# 05_can_spi.net
KiCad netlist of a schematic drawn in Altium Designer
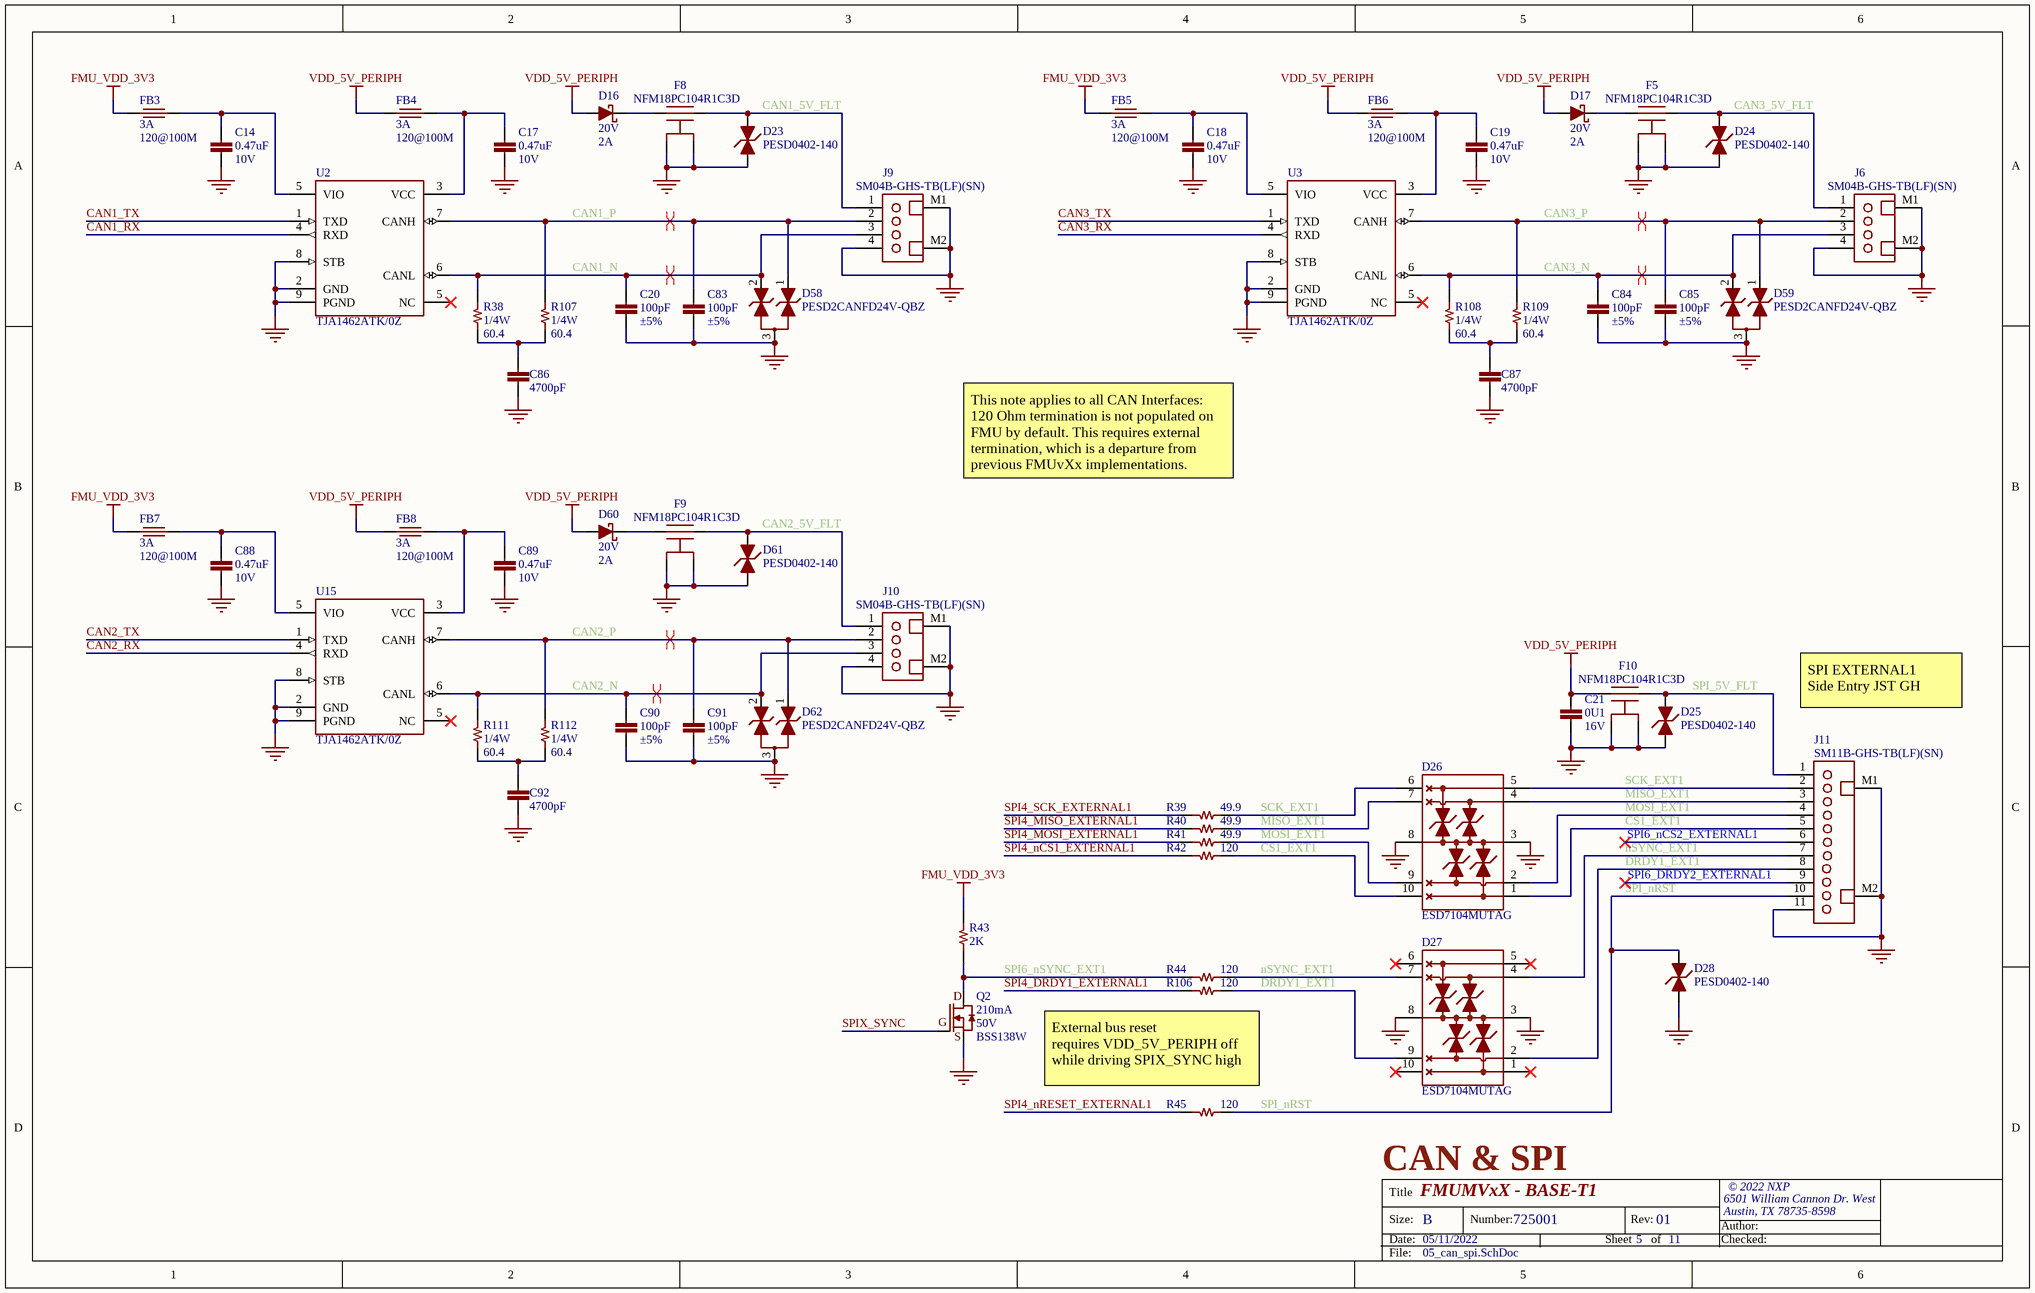
[diagram p0: 05_can_spi.SchDoc]

(export (version "E")
  (design (tool "Eeschema 10.0.6"))
  (components
    (comp (ref "C14")
      (value "0.47uF")
      (footprint "CAPC1608X90L30N")
      (description "CAP CER 0.47UF 10% 10V X7R 0603")
      (fields
        (field (name "TOLERANCE") "±10%")
        (field (name "MANUFACTURER") "Samsung Electro-Mechanics")
        (field (name "VOLTAGE - RATED") "10V")
      )
      (libsource (lib "NscDG_Integrated_Library") (part "CAP_0U47_10V_X7R_0603"))
    )
    (comp (ref "C17")
      (value "0.47uF")
      (footprint "CAPC1608X90L30N")
      (description "CAP CER 0.47UF 10% 10V X7R 0603")
      (fields
        (field (name "TOLERANCE") "±10%")
        (field (name "MANUFACTURER") "Samsung Electro-Mechanics")
        (field (name "VOLTAGE - RATED") "10V")
      )
      (libsource (lib "NscDG_Integrated_Library") (part "CAP_0U47_10V_X7R_0603"))
    )
    (comp (ref "C18")
      (value "0.47uF")
      (footprint "CAPC1608X90L30N")
      (description "CAP CER 0.47UF 10% 10V X7R 0603")
      (fields
        (field (name "TOLERANCE") "±10%")
        (field (name "MANUFACTURER") "Samsung Electro-Mechanics")
        (field (name "VOLTAGE - RATED") "10V")
      )
      (libsource (lib "NscDG_Integrated_Library") (part "CAP_0U47_10V_X7R_0603"))
    )
    (comp (ref "C19")
      (value "0.47uF")
      (footprint "CAPC1608X90L30N")
      (description "CAP CER 0.47UF 10% 10V X7R 0603")
      (fields
        (field (name "TOLERANCE") "±10%")
        (field (name "MANUFACTURER") "Samsung Electro-Mechanics")
        (field (name "VOLTAGE - RATED") "10V")
      )
      (libsource (lib "NscDG_Integrated_Library") (part "CAP_0U47_10V_X7R_0603"))
    )
    (comp (ref "C20")
      (value "100pF")
      (footprint "CAPC100X50X56L25N")
      (description "CAP CER 100PF +/-5% 50V COG/NPO 0402")
      (fields
        (field (name "MANUFACTURER") "Murata Electronics")
        (field (name "MANUFACTURER PART NUMBER") "GRM1555C1H101JA01D")
        (field (name "TOLERANCE") "±5%")
      )
      (libsource (lib "NscDG_Integrated_Library") (part "CAP_100PF_50V_COG/NPO_0402"))
    )
    (comp (ref "C21")
      (value "0U1")
      (footprint "CAPC100X50X56L25N")
      (description "CAP CER 0.1UF 10% 16V X7R 0402")
      (fields
        (field (name "TOLERANCE") "±10%")
        (field (name "MANUFACTURER") "Murata Electronics")
        (field (name "VOLTAGE - RATED") "16V")
      )
      (libsource (lib "NscDG_Integrated_Library") (part "CAP_0U1_16V_X7R_0402"))
    )
    (comp (ref "C83")
      (value "100pF")
      (footprint "CAPC100X50X56L25N")
      (description "CAP CER 100PF +/-5% 50V COG/NPO 0402")
      (fields
        (field (name "MANUFACTURER") "Murata Electronics")
        (field (name "MANUFACTURER PART NUMBER") "GRM1555C1H101JA01D")
        (field (name "TOLERANCE") "±5%")
      )
      (libsource (lib "NscDG_Integrated_Library") (part "CAP_100PF_50V_COG/NPO_0402"))
    )
    (comp (ref "C84")
      (value "100pF")
      (footprint "CAPC100X50X56L25N")
      (description "CAP CER 100PF +/-5% 50V COG/NPO 0402")
      (fields
        (field (name "MANUFACTURER") "Murata Electronics")
        (field (name "MANUFACTURER PART NUMBER") "GRM1555C1H101JA01D")
        (field (name "TOLERANCE") "±5%")
      )
      (libsource (lib "NscDG_Integrated_Library") (part "CAP_100PF_50V_COG/NPO_0402"))
    )
    (comp (ref "C85")
      (value "100pF")
      (footprint "CAPC100X50X56L25N")
      (description "CAP CER 100PF +/-5% 50V COG/NPO 0402")
      (fields
        (field (name "MANUFACTURER") "Murata Electronics")
        (field (name "MANUFACTURER PART NUMBER") "GRM1555C1H101JA01D")
        (field (name "TOLERANCE") "±5%")
      )
      (libsource (lib "NscDG_Integrated_Library") (part "CAP_100PF_50V_COG/NPO_0402"))
    )
    (comp (ref "C86")
      (value "4700pF")
      (footprint "CAPC100X50X56L25N")
      (description "CAP CER 4700PF 10% 50V X7R 0402")
      (fields
        (field (name "MANUFACTURER") "Murata Electronics")
        (field (name "MANUFACTURER PART NUMBER") "GRM155R71H472KA01J")
      )
      (libsource (lib "NscDG_Integrated_Library") (part "CAP_4700PF_5%_50V_X7R_0402"))
    )
    (comp (ref "C87")
      (value "4700pF")
      (footprint "CAPC100X50X56L25N")
      (description "CAP CER 4700PF 10% 50V X7R 0402")
      (fields
        (field (name "MANUFACTURER") "Murata Electronics")
        (field (name "MANUFACTURER PART NUMBER") "GRM155R71H472KA01J")
      )
      (libsource (lib "NscDG_Integrated_Library") (part "CAP_4700PF_5%_50V_X7R_0402"))
    )
    (comp (ref "C88")
      (value "0.47uF")
      (footprint "CAPC1608X90L30N")
      (description "CAP CER 0.47UF 10% 10V X7R 0603")
      (fields
        (field (name "TOLERANCE") "±10%")
        (field (name "MANUFACTURER") "Samsung Electro-Mechanics")
        (field (name "VOLTAGE - RATED") "10V")
      )
      (libsource (lib "NscDG_Integrated_Library") (part "CAP_0U47_10V_X7R_0603"))
    )
    (comp (ref "C89")
      (value "0.47uF")
      (footprint "CAPC1608X90L30N")
      (description "CAP CER 0.47UF 10% 10V X7R 0603")
      (fields
        (field (name "TOLERANCE") "±10%")
        (field (name "MANUFACTURER") "Samsung Electro-Mechanics")
        (field (name "VOLTAGE - RATED") "10V")
      )
      (libsource (lib "NscDG_Integrated_Library") (part "CAP_0U47_10V_X7R_0603"))
    )
    (comp (ref "C90")
      (value "100pF")
      (footprint "CAPC100X50X56L25N")
      (description "CAP CER 100PF +/-5% 50V COG/NPO 0402")
      (fields
        (field (name "MANUFACTURER") "Murata Electronics")
        (field (name "MANUFACTURER PART NUMBER") "GRM1555C1H101JA01D")
        (field (name "TOLERANCE") "±5%")
      )
      (libsource (lib "NscDG_Integrated_Library") (part "CAP_100PF_50V_COG/NPO_0402"))
    )
    (comp (ref "C91")
      (value "100pF")
      (footprint "CAPC100X50X56L25N")
      (description "CAP CER 100PF +/-5% 50V COG/NPO 0402")
      (fields
        (field (name "MANUFACTURER") "Murata Electronics")
        (field (name "MANUFACTURER PART NUMBER") "GRM1555C1H101JA01D")
        (field (name "TOLERANCE") "±5%")
      )
      (libsource (lib "NscDG_Integrated_Library") (part "CAP_100PF_50V_COG/NPO_0402"))
    )
    (comp (ref "C92")
      (value "4700pF")
      (footprint "CAPC100X50X56L25N")
      (description "CAP CER 4700PF 10% 50V X7R 0402")
      (fields
        (field (name "MANUFACTURER") "Murata Electronics")
        (field (name "MANUFACTURER PART NUMBER") "GRM155R71H472KA01J")
      )
      (libsource (lib "NscDG_Integrated_Library") (part "CAP_4700PF_5%_50V_X7R_0402"))
    )
    (comp (ref "D16")
      (value "DIODE SCHOTTKY 20V 2A DFN1608D-2")
      (footprint "DIODFN2_160X80X40L34X71N")
      (fields
        (field (name "MANUFACTURER") "Nexperia USA Inc.")
        (field (name "MANUFACTURER PART NUMBER") "PMEG2020EPK,315")
        (field (name "VOLTAGE") "20V")
        (field (name "CURRENT") "2A")
      )
      (libsource (lib "NscDG_Integrated_Library") (part "DIODE_SCHOTTKY_20V_2A_DFN1608D-2"))
    )
    (comp (ref "D17")
      (value "DIODE SCHOTTKY 20V 2A DFN1608D-2")
      (footprint "DIODFN2_160X80X40L34X71N")
      (fields
        (field (name "MANUFACTURER") "Nexperia USA Inc.")
        (field (name "MANUFACTURER PART NUMBER") "PMEG2020EPK,315")
        (field (name "VOLTAGE") "20V")
        (field (name "CURRENT") "2A")
      )
      (libsource (lib "NscDG_Integrated_Library") (part "DIODE_SCHOTTKY_20V_2A_DFN1608D-2"))
    )
    (comp (ref "D23")
      (value "DIODE TVS BIDIRECTIONAL 14VWM 40VC 0402")
      (footprint "DIONC100X50X43L20N")
      (fields
        (field (name "MANUFACTURER") "Littelfuse Inc.")
        (field (name "MANUFACTURER PART NUMBER") "PESD0402-140")
      )
      (libsource (lib "NscDG_Integrated_Library") (part "DIODE_TVS_0402"))
    )
    (comp (ref "D24")
      (value "DIODE TVS BIDIRECTIONAL 14VWM 40VC 0402")
      (footprint "DIONC100X50X43L20N")
      (fields
        (field (name "MANUFACTURER") "Littelfuse Inc.")
        (field (name "MANUFACTURER PART NUMBER") "PESD0402-140")
      )
      (libsource (lib "NscDG_Integrated_Library") (part "DIODE_TVS_0402"))
    )
    (comp (ref "D25")
      (value "DIODE TVS BIDIRECTIONAL 14VWM 40VC 0402")
      (footprint "DIONC100X50X43L20N")
      (fields
        (field (name "MANUFACTURER") "Littelfuse Inc.")
        (field (name "MANUFACTURER PART NUMBER") "PESD0402-140")
      )
      (libsource (lib "NscDG_Integrated_Library") (part "DIODE_TVS_0402"))
    )
    (comp (ref "D26")
      (value "DIODE TVS BIDIRECTIONAL 5V 10V 10UDFN")
      (footprint "UDFN10P50_250X100X55L35X20N")
      (fields
        (field (name "MANUFACTURER") "ON Semiconductor")
        (field (name "MANUFACTURER PART NUMBER") "ESD7104MUTAG")
      )
      (libsource (lib "NscDG_Integrated_Library") (part "DIODE_TVS_4X_10UDFN"))
    )
    (comp (ref "D27")
      (value "DIODE TVS BIDIRECTIONAL 5V 10V 10UDFN")
      (footprint "UDFN10P50_250X100X55L35X20N")
      (fields
        (field (name "MANUFACTURER") "ON Semiconductor")
        (field (name "MANUFACTURER PART NUMBER") "ESD7104MUTAG")
      )
      (libsource (lib "NscDG_Integrated_Library") (part "DIODE_TVS_4X_10UDFN"))
    )
    (comp (ref "D28")
      (value "DIODE TVS BIDIRECTIONAL 14VWM 40VC 0402")
      (footprint "DIONC100X50X43L20N")
      (fields
        (field (name "MANUFACTURER") "Littelfuse Inc.")
        (field (name "MANUFACTURER PART NUMBER") "PESD0402-140")
      )
      (libsource (lib "NscDG_Integrated_Library") (part "DIODE_TVS_0402"))
    )
    (comp (ref "D58")
      (value "DIODE TVS DUAL 42V CLAMP 2.6A (8/20us) DFN1110D-3")
      (footprint "NEXPERIA_SOT8015")
      (fields
        (field (name "VOLTAGE") "42V")
        (field (name "MANUFACTURER") "Nexperia USA Inc.")
        (field (name "MANUFACTURER PART NUMBER") "PESD2CANFD24V-QBZ")
      )
      (libsource (lib "NscDG_Integrated_Library") (part "DIODE_TVS_DUAL_24VWM_42VC_DFN1110D-3"))
    )
    (comp (ref "D59")
      (value "DIODE TVS DUAL 42V CLAMP 2.6A (8/20us) DFN1110D-3")
      (footprint "NEXPERIA_SOT8015")
      (fields
        (field (name "VOLTAGE") "42V")
        (field (name "MANUFACTURER") "Nexperia USA Inc.")
        (field (name "MANUFACTURER PART NUMBER") "PESD2CANFD24V-QBZ")
      )
      (libsource (lib "NscDG_Integrated_Library") (part "DIODE_TVS_DUAL_24VWM_42VC_DFN1110D-3"))
    )
    (comp (ref "D60")
      (value "DIODE SCHOTTKY 20V 2A DFN1608D-2")
      (footprint "DIODFN2_160X80X40L34X71N")
      (fields
        (field (name "MANUFACTURER") "Nexperia USA Inc.")
        (field (name "MANUFACTURER PART NUMBER") "PMEG2020EPK,315")
        (field (name "VOLTAGE") "20V")
        (field (name "CURRENT") "2A")
      )
      (libsource (lib "NscDG_Integrated_Library") (part "DIODE_SCHOTTKY_20V_2A_DFN1608D-2"))
    )
    (comp (ref "D61")
      (value "DIODE TVS BIDIRECTIONAL 14VWM 40VC 0402")
      (footprint "DIONC100X50X43L20N")
      (fields
        (field (name "MANUFACTURER") "Littelfuse Inc.")
        (field (name "MANUFACTURER PART NUMBER") "PESD0402-140")
      )
      (libsource (lib "NscDG_Integrated_Library") (part "DIODE_TVS_0402"))
    )
    (comp (ref "D62")
      (value "DIODE TVS DUAL 42V CLAMP 2.6A (8/20us) DFN1110D-3")
      (footprint "NEXPERIA_SOT8015")
      (fields
        (field (name "VOLTAGE") "42V")
        (field (name "MANUFACTURER") "Nexperia USA Inc.")
        (field (name "MANUFACTURER PART NUMBER") "PESD2CANFD24V-QBZ")
      )
      (libsource (lib "NscDG_Integrated_Library") (part "DIODE_TVS_DUAL_24VWM_42VC_DFN1110D-3"))
    )
    (comp (ref "F5")
      (value "FILTER CAP FEEDTHRU 0.1UF 20% 16V 0603")
      (footprint "NFM18PC104R1C3_0603_NO_VIA")
      (fields
        (field (name "TOLERANCE") "±20%")
        (field (name "MANUFACTURER") "Murata Electronics North America")
        (field (name "MANUFACTURER PART NUMBER") "NFM18PC104R1C3D")
      )
      (libsource (lib "NscDG_Integrated_Library") (part "FILTER_0.1uF_16V_2A_NO_VIA_0603"))
    )
    (comp (ref "F8")
      (value "FILTER CAP FEEDTHRU 0.1UF 20% 16V 0603")
      (footprint "NFM18PC104R1C3_0603_NO_VIA")
      (fields
        (field (name "TOLERANCE") "±20%")
        (field (name "MANUFACTURER") "Murata Electronics North America")
        (field (name "MANUFACTURER PART NUMBER") "NFM18PC104R1C3D")
      )
      (libsource (lib "NscDG_Integrated_Library") (part "FILTER_0.1uF_16V_2A_NO_VIA_0603"))
    )
    (comp (ref "F9")
      (value "FILTER CAP FEEDTHRU 0.1UF 20% 16V 0603")
      (footprint "NFM18PC104R1C3_0603_NO_VIA")
      (fields
        (field (name "TOLERANCE") "±20%")
        (field (name "MANUFACTURER") "Murata Electronics North America")
        (field (name "MANUFACTURER PART NUMBER") "NFM18PC104R1C3D")
      )
      (libsource (lib "NscDG_Integrated_Library") (part "FILTER_0.1uF_16V_2A_NO_VIA_0603"))
    )
    (comp (ref "F10")
      (value "FILTER CAP FEEDTHRU 0.1UF 20% 16V 0603")
      (footprint "NFM18PC104R1C3_0603_NO_VIA")
      (fields
        (field (name "TOLERANCE") "±20%")
        (field (name "MANUFACTURER") "Murata Electronics North America")
        (field (name "MANUFACTURER PART NUMBER") "NFM18PC104R1C3D")
      )
      (libsource (lib "NscDG_Integrated_Library") (part "FILTER_0.1uF_16V_2A_NO_VIA_0603"))
    )
    (comp (ref "FB3")
      (value "120@100M")
      (footprint "BEADC160X80X95L36N")
      (description "IND FERRITE 120@100M 3A 20mOhm 0603")
      (fields
        (field (name "MANUFACTURER") "Murata Electronics")
        (field (name "MANUFACTURER PART NUMBER") "BLM18KG121TZ1D")
        (field (name "CURRENT") "3A")
      )
      (libsource (lib "NscDG_Integrated_Library") (part "IND_FERRITE_120@100M_3A_0603"))
    )
    (comp (ref "FB4")
      (value "120@100M")
      (footprint "BEADC160X80X95L36N")
      (description "IND FERRITE 120@100M 3A 20mOhm 0603")
      (fields
        (field (name "MANUFACTURER") "Murata Electronics")
        (field (name "MANUFACTURER PART NUMBER") "BLM18KG121TZ1D")
        (field (name "CURRENT") "3A")
      )
      (libsource (lib "NscDG_Integrated_Library") (part "IND_FERRITE_120@100M_3A_0603"))
    )
    (comp (ref "FB5")
      (value "120@100M")
      (footprint "BEADC160X80X95L36N")
      (description "IND FERRITE 120@100M 3A 20mOhm 0603")
      (fields
        (field (name "MANUFACTURER") "Murata Electronics")
        (field (name "MANUFACTURER PART NUMBER") "BLM18KG121TZ1D")
        (field (name "CURRENT") "3A")
      )
      (libsource (lib "NscDG_Integrated_Library") (part "IND_FERRITE_120@100M_3A_0603"))
    )
    (comp (ref "FB6")
      (value "120@100M")
      (footprint "BEADC160X80X95L36N")
      (description "IND FERRITE 120@100M 3A 20mOhm 0603")
      (fields
        (field (name "MANUFACTURER") "Murata Electronics")
        (field (name "MANUFACTURER PART NUMBER") "BLM18KG121TZ1D")
        (field (name "CURRENT") "3A")
      )
      (libsource (lib "NscDG_Integrated_Library") (part "IND_FERRITE_120@100M_3A_0603"))
    )
    (comp (ref "FB7")
      (value "120@100M")
      (footprint "BEADC160X80X95L36N")
      (description "IND FERRITE 120@100M 3A 20mOhm 0603")
      (fields
        (field (name "MANUFACTURER") "Murata Electronics")
        (field (name "MANUFACTURER PART NUMBER") "BLM18KG121TZ1D")
        (field (name "CURRENT") "3A")
      )
      (libsource (lib "NscDG_Integrated_Library") (part "IND_FERRITE_120@100M_3A_0603"))
    )
    (comp (ref "FB8")
      (value "120@100M")
      (footprint "BEADC160X80X95L36N")
      (description "IND FERRITE 120@100M 3A 20mOhm 0603")
      (fields
        (field (name "MANUFACTURER") "Murata Electronics")
        (field (name "MANUFACTURER PART NUMBER") "BLM18KG121TZ1D")
        (field (name "CURRENT") "3A")
      )
      (libsource (lib "NscDG_Integrated_Library") (part "IND_FERRITE_120@100M_3A_0603"))
    )
    (comp (ref "J6")
      (value "CONN HEADER GH SIDE 4POS 1.25MM SMT")
      (footprint "JST_SM04B-GHS-TBLFSN")
      (fields
        (field (name "MANUFACTURER") "JST Sales America Inc.")
        (field (name "MANUFACTURER PART NUMBER") "SM04B-GHS-TB(LF)(SN)")
      )
      (libsource (lib "NscDG_Integrated_Library") (part "CONN_JST_GH_4PIN_RA_SMT"))
    )
    (comp (ref "J9")
      (value "CONN HEADER GH SIDE 4POS 1.25MM SMT")
      (footprint "JST_SM04B-GHS-TBLFSN")
      (fields
        (field (name "MANUFACTURER") "JST Sales America Inc.")
        (field (name "MANUFACTURER PART NUMBER") "SM04B-GHS-TB(LF)(SN)")
      )
      (libsource (lib "NscDG_Integrated_Library") (part "CONN_JST_GH_4PIN_RA_SMT"))
    )
    (comp (ref "J10")
      (value "CONN HEADER GH SIDE 4POS 1.25MM SMT")
      (footprint "JST_SM04B-GHS-TBLFSN")
      (fields
        (field (name "MANUFACTURER") "JST Sales America Inc.")
        (field (name "MANUFACTURER PART NUMBER") "SM04B-GHS-TB(LF)(SN)")
      )
      (libsource (lib "NscDG_Integrated_Library") (part "CONN_JST_GH_4PIN_RA_SMT"))
    )
    (comp (ref "J11")
      (value "CONN HEADER GH 11POS SIDE 1.25MM SMT")
      (footprint "JST_SM11B-GHS-TBLFSN")
      (fields
        (field (name "MANUFACTURER") "JST Sales America Inc.")
        (field (name "MANUFACTURER PART NUMBER") "SM11B-GHS-TB(LF)(SN)")
      )
      (libsource (lib "NscDG_Integrated_Library") (part "CONN_JST_GH_11PIN_RA_SMT"))
    )
    (comp (ref "Q2")
      (value "TRANSISTOR N-CH 50V .21A  SC-70")
      (footprint "OnSemi_SC-70-3P65_210X110L20X32N")
      (fields
        (field (name "MANUFACTURER") "ON Semiconductor")
        (field (name "CURRENT") "210mA")
        (field (name "VOLTAGE") "50V")
        (field (name "MANUFACTURER PART NUMBER") "BSS138W")
      )
      (libsource (lib "NscDG_Integrated_Library") (part "TRAN_MOSFET_N-CH_BSS138W_SMT"))
    )
    (comp (ref "R38")
      (value "60.4")
      (footprint "RESC1608X55L30N")
      (description "RES 60.4 1% 1/4W 0603")
      (fields
        (field (name "TOLERANCE") "±1%")
        (field (name "MANUFACTURER") "Vishay Dale")
        (field (name "POWER") "1/4W")
      )
      (libsource (lib "NscDG_Integrated_Library") (part "RES_60.4_1%_1/4W_0603"))
    )
    (comp (ref "R39")
      (value "49.9")
      (footprint "RESC100X50X40L25")
      (description "RES SMD 49R9 OHM 1% 1/16W 0402")
      (fields (field (name "TOLERANCE") "±1%") (field (name "MANUFACTURER") "Yageo"))
      (libsource (lib "NscDG_Integrated_Library") (part "RES_49.9_1%_1/16W_0402"))
    )
    (comp (ref "R40")
      (value "49.9")
      (footprint "RESC100X50X40L25")
      (description "RES SMD 49R9 OHM 1% 1/16W 0402")
      (fields (field (name "TOLERANCE") "±1%") (field (name "MANUFACTURER") "Yageo"))
      (libsource (lib "NscDG_Integrated_Library") (part "RES_49.9_1%_1/16W_0402"))
    )
    (comp (ref "R41")
      (value "49.9")
      (footprint "RESC100X50X40L25")
      (description "RES SMD 49R9 OHM 1% 1/16W 0402")
      (fields (field (name "TOLERANCE") "±1%") (field (name "MANUFACTURER") "Yageo"))
      (libsource (lib "NscDG_Integrated_Library") (part "RES_49.9_1%_1/16W_0402"))
    )
    (comp (ref "R42")
      (value "120")
      (footprint "RESC100X50X40L25")
      (description "RES SMD 120 OHM 1% 1/16W 0402")
      (fields (field (name "TOLERANCE") "±1%") (field (name "MANUFACTURER") "Yageo"))
      (libsource (lib "NscDG_Integrated_Library") (part "RES_120_1%_1/16W_0402"))
    )
    (comp (ref "R43")
      (value "2K")
      (footprint "RESC100X50X40L25")
      (description "RES SMD 2K OHM 1% 1/16W 0402")
      (fields (field (name "TOLERANCE") "±1%") (field (name "MANUFACTURER") "Yageo"))
      (libsource (lib "NscDG_Integrated_Library") (part "RES_2K_1%_1/16W_0402"))
    )
    (comp (ref "R44")
      (value "120")
      (footprint "RESC100X50X40L25")
      (description "RES SMD 120 OHM 1% 1/16W 0402")
      (fields (field (name "TOLERANCE") "±1%") (field (name "MANUFACTURER") "Yageo"))
      (libsource (lib "NscDG_Integrated_Library") (part "RES_120_1%_1/16W_0402"))
    )
    (comp (ref "R45")
      (value "120")
      (footprint "RESC100X50X40L25")
      (description "RES SMD 120 OHM 1% 1/16W 0402")
      (fields (field (name "TOLERANCE") "±1%") (field (name "MANUFACTURER") "Yageo"))
      (libsource (lib "NscDG_Integrated_Library") (part "RES_120_1%_1/16W_0402"))
    )
    (comp (ref "R106")
      (value "120")
      (footprint "RESC100X50X40L25")
      (description "RES SMD 120 OHM 1% 1/16W 0402")
      (fields (field (name "TOLERANCE") "±1%") (field (name "MANUFACTURER") "Yageo"))
      (libsource (lib "NscDG_Integrated_Library") (part "RES_120_1%_1/16W_0402"))
    )
    (comp (ref "R107")
      (value "60.4")
      (footprint "RESC1608X55L30N")
      (description "RES 60.4 1% 1/4W 0603")
      (fields
        (field (name "TOLERANCE") "±1%")
        (field (name "MANUFACTURER") "Vishay Dale")
        (field (name "POWER") "1/4W")
      )
      (libsource (lib "NscDG_Integrated_Library") (part "RES_60.4_1%_1/4W_0603"))
    )
    (comp (ref "R108")
      (value "60.4")
      (footprint "RESC1608X55L30N")
      (description "RES 60.4 1% 1/4W 0603")
      (fields
        (field (name "TOLERANCE") "±1%")
        (field (name "MANUFACTURER") "Vishay Dale")
        (field (name "POWER") "1/4W")
      )
      (libsource (lib "NscDG_Integrated_Library") (part "RES_60.4_1%_1/4W_0603"))
    )
    (comp (ref "R109")
      (value "60.4")
      (footprint "RESC1608X55L30N")
      (description "RES 60.4 1% 1/4W 0603")
      (fields
        (field (name "TOLERANCE") "±1%")
        (field (name "MANUFACTURER") "Vishay Dale")
        (field (name "POWER") "1/4W")
      )
      (libsource (lib "NscDG_Integrated_Library") (part "RES_60.4_1%_1/4W_0603"))
    )
    (comp (ref "R111")
      (value "60.4")
      (footprint "RESC1608X55L30N")
      (description "RES 60.4 1% 1/4W 0603")
      (fields
        (field (name "TOLERANCE") "±1%")
        (field (name "MANUFACTURER") "Vishay Dale")
        (field (name "POWER") "1/4W")
      )
      (libsource (lib "NscDG_Integrated_Library") (part "RES_60.4_1%_1/4W_0603"))
    )
    (comp (ref "R112")
      (value "60.4")
      (footprint "RESC1608X55L30N")
      (description "RES 60.4 1% 1/4W 0603")
      (fields
        (field (name "TOLERANCE") "±1%")
        (field (name "MANUFACTURER") "Vishay Dale")
        (field (name "POWER") "1/4W")
      )
      (libsource (lib "NscDG_Integrated_Library") (part "RES_60.4_1%_1/4W_0603"))
    )
    (comp (ref "U2")
      (value "IC CAN TRANSCEIVER HALF 1/1 8-HVSON")
      (footprint "SON9P65_300X300X100L40X30T240X160_RECT_TABN")
      (fields
        (field (name "MANUFACTURER") "NXP USA Inc.")
        (field (name "MANUFACTURER PART NUMBER") "TJA1462ATK/0Z")
      )
      (libsource (lib "NscDG_Integrated_Library") (part "IC_TJA1462ATK/0Z_8-HVSON"))
    )
    (comp (ref "U3")
      (value "IC CAN TRANSCEIVER HALF 1/1 8-HVSON")
      (footprint "SON9P65_300X300X100L40X30T240X160_RECT_TABN")
      (fields
        (field (name "MANUFACTURER") "NXP USA Inc.")
        (field (name "MANUFACTURER PART NUMBER") "TJA1462ATK/0Z")
      )
      (libsource (lib "NscDG_Integrated_Library") (part "IC_TJA1462ATK/0Z_8-HVSON"))
    )
    (comp (ref "U15")
      (value "IC CAN TRANSCEIVER HALF 1/1 8-HVSON")
      (footprint "SON9P65_300X300X100L40X30T240X160_RECT_TABN")
      (fields
        (field (name "MANUFACTURER") "NXP USA Inc.")
        (field (name "MANUFACTURER PART NUMBER") "TJA1462ATK/0Z")
      )
      (libsource (lib "NscDG_Integrated_Library") (part "IC_TJA1462ATK/0Z_8-HVSON"))
    )
  )
  (nets
    (net (code "1") (name "/CAN1_5V_FLT") (class "Default")
      (node (ref "D23") (pin "2") (pinfunction "2_2") (pintype "passive"))
      (node (ref "F8") (pin "3") (pinfunction "3_3") (pintype "passive"))
      (node (ref "J9") (pin "1") (pinfunction "1_1") (pintype "passive"))
    )
    (net (code "2") (name "/CAN1_N") (class "Default")
      (node (ref "C20") (pin "1") (pinfunction "1_1") (pintype "passive"))
      (node (ref "D58") (pin "2") (pinfunction "2_2") (pintype "passive"))
      (node (ref "J9") (pin "3") (pinfunction "3_3") (pintype "passive"))
      (node (ref "R38") (pin "1") (pinfunction "1_1") (pintype "passive"))
      (node (ref "U2") (pin "6") (pinfunction "CANL_6") (pintype "bidirectional"))
    )
    (net (code "3") (name "/CAN1_P") (class "Default")
      (node (ref "C83") (pin "1") (pinfunction "1_1") (pintype "passive"))
      (node (ref "D58") (pin "1") (pinfunction "1_1") (pintype "passive"))
      (node (ref "J9") (pin "2") (pinfunction "2_2") (pintype "passive"))
      (node (ref "R107") (pin "1") (pinfunction "1_1") (pintype "passive"))
      (node (ref "U2") (pin "7") (pinfunction "CANH_7") (pintype "bidirectional"))
    )
    (net (code "4") (name "/CAN1_RX") (class "Default")
      (node (ref "U2") (pin "4") (pinfunction "RXD_4") (pintype "output"))
    )
    (net (code "5") (name "/CAN1_TX") (class "Default")
      (node (ref "U2") (pin "1") (pinfunction "TXD_1") (pintype "input"))
    )
    (net (code "6") (name "/CAN2_5V_FLT") (class "Default")
      (node (ref "D61") (pin "2") (pinfunction "2_2") (pintype "passive"))
      (node (ref "F9") (pin "3") (pinfunction "3_3") (pintype "passive"))
      (node (ref "J10") (pin "1") (pinfunction "1_1") (pintype "passive"))
    )
    (net (code "7") (name "/CAN2_N") (class "Default")
      (node (ref "C90") (pin "1") (pinfunction "1_1") (pintype "passive"))
      (node (ref "D62") (pin "2") (pinfunction "2_2") (pintype "passive"))
      (node (ref "J10") (pin "3") (pinfunction "3_3") (pintype "passive"))
      (node (ref "R111") (pin "1") (pinfunction "1_1") (pintype "passive"))
      (node (ref "U15") (pin "6") (pinfunction "CANL_6") (pintype "bidirectional"))
    )
    (net (code "8") (name "/CAN2_P") (class "Default")
      (node (ref "C91") (pin "1") (pinfunction "1_1") (pintype "passive"))
      (node (ref "D62") (pin "1") (pinfunction "1_1") (pintype "passive"))
      (node (ref "J10") (pin "2") (pinfunction "2_2") (pintype "passive"))
      (node (ref "R112") (pin "1") (pinfunction "1_1") (pintype "passive"))
      (node (ref "U15") (pin "7") (pinfunction "CANH_7") (pintype "bidirectional"))
    )
    (net (code "9") (name "/CAN2_RX") (class "Default")
      (node (ref "U15") (pin "4") (pinfunction "RXD_4") (pintype "output"))
    )
    (net (code "10") (name "/CAN2_TX") (class "Default")
      (node (ref "U15") (pin "1") (pinfunction "TXD_1") (pintype "input"))
    )
    (net (code "11") (name "/CAN3_5V_FLT") (class "Default")
      (node (ref "D24") (pin "2") (pinfunction "2_2") (pintype "passive"))
      (node (ref "F5") (pin "3") (pinfunction "3_3") (pintype "passive"))
      (node (ref "J6") (pin "1") (pinfunction "1_1") (pintype "passive"))
    )
    (net (code "12") (name "/CAN3_N") (class "Default")
      (node (ref "C84") (pin "1") (pinfunction "1_1") (pintype "passive"))
      (node (ref "D59") (pin "2") (pinfunction "2_2") (pintype "passive"))
      (node (ref "J6") (pin "3") (pinfunction "3_3") (pintype "passive"))
      (node (ref "R108") (pin "1") (pinfunction "1_1") (pintype "passive"))
      (node (ref "U3") (pin "6") (pinfunction "CANL_6") (pintype "bidirectional"))
    )
    (net (code "13") (name "/CAN3_P") (class "Default")
      (node (ref "C85") (pin "1") (pinfunction "1_1") (pintype "passive"))
      (node (ref "D59") (pin "1") (pinfunction "1_1") (pintype "passive"))
      (node (ref "J6") (pin "2") (pinfunction "2_2") (pintype "passive"))
      (node (ref "R109") (pin "1") (pinfunction "1_1") (pintype "passive"))
      (node (ref "U3") (pin "7") (pinfunction "CANH_7") (pintype "bidirectional"))
    )
    (net (code "14") (name "/CAN3_RX") (class "Default")
      (node (ref "U3") (pin "4") (pinfunction "RXD_4") (pintype "output"))
    )
    (net (code "15") (name "/CAN3_TX") (class "Default")
      (node (ref "U3") (pin "1") (pinfunction "TXD_1") (pintype "input"))
    )
    (net (code "16") (name "/CS1_EXT1") (class "Default")
      (node (ref "D26") (pin "1") (pinfunction "1_1") (pintype "passive"))
      (node (ref "D26") (pin "10") (pinfunction "NC_10") (pintype "passive"))
      (node (ref "J11") (pin "5") (pinfunction "5_5") (pintype "passive"))
      (node (ref "R42") (pin "2") (pinfunction "2_2") (pintype "passive"))
    )
    (net (code "17") (name "/DRDY1_EXT1") (class "Default")
      (node (ref "D27") (pin "2") (pinfunction "2_2") (pintype "passive"))
      (node (ref "D27") (pin "9") (pinfunction "NC_9") (pintype "passive"))
      (node (ref "J11") (pin "8") (pinfunction "8_8") (pintype "passive"))
      (node (ref "R106") (pin "2") (pinfunction "2_2") (pintype "passive"))
    )
    (net (code "18") (name "/MISO_EXT1") (class "Default")
      (node (ref "D26") (pin "4") (pinfunction "4_4") (pintype "passive"))
      (node (ref "D26") (pin "7") (pinfunction "NC_7") (pintype "passive"))
      (node (ref "J11") (pin "3") (pinfunction "3_3") (pintype "passive"))
      (node (ref "R40") (pin "2") (pinfunction "2_2") (pintype "passive"))
    )
    (net (code "19") (name "/MOSI_EXT1") (class "Default")
      (node (ref "D26") (pin "2") (pinfunction "2_2") (pintype "passive"))
      (node (ref "D26") (pin "9") (pinfunction "NC_9") (pintype "passive"))
      (node (ref "J11") (pin "4") (pinfunction "4_4") (pintype "passive"))
      (node (ref "R41") (pin "2") (pinfunction "2_2") (pintype "passive"))
    )
    (net (code "20") (name "/SCK_EXT1") (class "Default")
      (node (ref "D26") (pin "5") (pinfunction "5_5") (pintype "passive"))
      (node (ref "D26") (pin "6") (pinfunction "NC_6") (pintype "passive"))
      (node (ref "J11") (pin "2") (pinfunction "2_2") (pintype "passive"))
      (node (ref "R39") (pin "2") (pinfunction "2_2") (pintype "passive"))
    )
    (net (code "21") (name "/SPI4_DRDY1_EXTERNAL1") (class "Default")
      (node (ref "R106") (pin "1") (pinfunction "1_1") (pintype "passive"))
    )
    (net (code "22") (name "/SPI4_MISO_EXTERNAL1") (class "Default")
      (node (ref "R40") (pin "1") (pinfunction "1_1") (pintype "passive"))
    )
    (net (code "23") (name "/SPI4_MOSI_EXTERNAL1") (class "Default")
      (node (ref "R41") (pin "1") (pinfunction "1_1") (pintype "passive"))
    )
    (net (code "24") (name "/SPI4_SCK_EXTERNAL1") (class "Default")
      (node (ref "R39") (pin "1") (pinfunction "1_1") (pintype "passive"))
    )
    (net (code "25") (name "/SPI4_nCS1_EXTERNAL1") (class "Default")
      (node (ref "R42") (pin "1") (pinfunction "1_1") (pintype "passive"))
    )
    (net (code "26") (name "/SPI4_nRESET_EXTERNAL1") (class "Default")
      (node (ref "R45") (pin "1") (pinfunction "1_1") (pintype "passive"))
    )
    (net (code "27") (name "/SPI6_nSYNC_EXT1") (class "Default")
      (node (ref "Q2") (pin "D") (pinfunction "D_D") (pintype "passive"))
      (node (ref "R43") (pin "2") (pinfunction "2_2") (pintype "passive"))
      (node (ref "R44") (pin "1") (pinfunction "1_1") (pintype "passive"))
    )
    (net (code "28") (name "/SPIX_SYNC") (class "Default")
      (node (ref "Q2") (pin "G") (pinfunction "G_G") (pintype "passive"))
    )
    (net (code "29") (name "/SPI_5V_FLT") (class "Default")
      (node (ref "D25") (pin "2") (pinfunction "2_2") (pintype "passive"))
      (node (ref "F10") (pin "3") (pinfunction "3_3") (pintype "passive"))
      (node (ref "J11") (pin "1") (pinfunction "1_1") (pintype "passive"))
    )
    (net (code "30") (name "/SPI_nRST") (class "Default")
      (node (ref "D28") (pin "2") (pinfunction "2_2") (pintype "passive"))
      (node (ref "J11") (pin "10") (pinfunction "10_10") (pintype "passive"))
      (node (ref "R45") (pin "2") (pinfunction "2_2") (pintype "passive"))
    )
    (net (code "31") (name "/nSYNC_EXT1") (class "Default")
      (node (ref "D27") (pin "4") (pinfunction "4_4") (pintype "passive"))
      (node (ref "D27") (pin "7") (pinfunction "NC_7") (pintype "passive"))
      (node (ref "J11") (pin "7") (pinfunction "7_7") (pintype "passive"))
      (node (ref "R44") (pin "2") (pinfunction "2_2") (pintype "passive"))
    )
    (net (code "32") (name "FMU_VDD_3V3") (class "Default")
      (node (ref "FB3") (pin "1") (pinfunction "1_1") (pintype "passive"))
      (node (ref "FB5") (pin "1") (pinfunction "1_1") (pintype "passive"))
      (node (ref "FB7") (pin "1") (pinfunction "1_1") (pintype "passive"))
      (node (ref "R43") (pin "1") (pinfunction "1_1") (pintype "passive"))
    )
    (net (code "33") (name "GND") (class "Default")
      (node (ref "C14") (pin "2") (pinfunction "2_2") (pintype "passive"))
      (node (ref "C17") (pin "2") (pinfunction "2_2") (pintype "passive"))
      (node (ref "C18") (pin "2") (pinfunction "2_2") (pintype "passive"))
      (node (ref "C19") (pin "2") (pinfunction "2_2") (pintype "passive"))
      (node (ref "C20") (pin "2") (pinfunction "2_2") (pintype "passive"))
      (node (ref "C21") (pin "2") (pinfunction "2_2") (pintype "passive"))
      (node (ref "C83") (pin "2") (pinfunction "2_2") (pintype "passive"))
      (node (ref "C84") (pin "2") (pinfunction "2_2") (pintype "passive"))
      (node (ref "C85") (pin "2") (pinfunction "2_2") (pintype "passive"))
      (node (ref "C86") (pin "2") (pinfunction "2_2") (pintype "passive"))
      (node (ref "C87") (pin "2") (pinfunction "2_2") (pintype "passive"))
      (node (ref "C88") (pin "2") (pinfunction "2_2") (pintype "passive"))
      (node (ref "C89") (pin "2") (pinfunction "2_2") (pintype "passive"))
      (node (ref "C90") (pin "2") (pinfunction "2_2") (pintype "passive"))
      (node (ref "C91") (pin "2") (pinfunction "2_2") (pintype "passive"))
      (node (ref "C92") (pin "2") (pinfunction "2_2") (pintype "passive"))
      (node (ref "D23") (pin "1") (pinfunction "1_1") (pintype "passive"))
      (node (ref "D24") (pin "1") (pinfunction "1_1") (pintype "passive"))
      (node (ref "D25") (pin "1") (pinfunction "1_1") (pintype "passive"))
      (node (ref "D26") (pin "3") (pinfunction "GND_3") (pintype "passive"))
      (node (ref "D26") (pin "8") (pinfunction "GND_8") (pintype "passive"))
      (node (ref "D27") (pin "3") (pinfunction "GND_3") (pintype "passive"))
      (node (ref "D27") (pin "8") (pinfunction "GND_8") (pintype "passive"))
      (node (ref "D28") (pin "1") (pinfunction "1_1") (pintype "passive"))
      (node (ref "D58") (pin "3") (pinfunction "3_3") (pintype "passive"))
      (node (ref "D59") (pin "3") (pinfunction "3_3") (pintype "passive"))
      (node (ref "D61") (pin "1") (pinfunction "1_1") (pintype "passive"))
      (node (ref "D62") (pin "3") (pinfunction "3_3") (pintype "passive"))
      (node (ref "F10") (pin "2A") (pinfunction "GND_2A") (pintype "passive"))
      (node (ref "F10") (pin "2B") (pinfunction "GND_2B") (pintype "passive"))
      (node (ref "F5") (pin "2A") (pinfunction "GND_2A") (pintype "passive"))
      (node (ref "F5") (pin "2B") (pinfunction "GND_2B") (pintype "passive"))
      (node (ref "F8") (pin "2A") (pinfunction "GND_2A") (pintype "passive"))
      (node (ref "F8") (pin "2B") (pinfunction "GND_2B") (pintype "passive"))
      (node (ref "F9") (pin "2A") (pinfunction "GND_2A") (pintype "passive"))
      (node (ref "F9") (pin "2B") (pinfunction "GND_2B") (pintype "passive"))
      (node (ref "J10") (pin "4") (pinfunction "4_4") (pintype "passive"))
      (node (ref "J10") (pin "M1") (pinfunction "M1_M1") (pintype "passive"))
      (node (ref "J10") (pin "M2") (pinfunction "M2_M2") (pintype "passive"))
      (node (ref "J11") (pin "11") (pinfunction "11_11") (pintype "passive"))
      (node (ref "J11") (pin "M1") (pinfunction "M1_M1") (pintype "passive"))
      (node (ref "J11") (pin "M2") (pinfunction "M2_M2") (pintype "passive"))
      (node (ref "J6") (pin "4") (pinfunction "4_4") (pintype "passive"))
      (node (ref "J6") (pin "M1") (pinfunction "M1_M1") (pintype "passive"))
      (node (ref "J6") (pin "M2") (pinfunction "M2_M2") (pintype "passive"))
      (node (ref "J9") (pin "4") (pinfunction "4_4") (pintype "passive"))
      (node (ref "J9") (pin "M1") (pinfunction "M1_M1") (pintype "passive"))
      (node (ref "J9") (pin "M2") (pinfunction "M2_M2") (pintype "passive"))
      (node (ref "Q2") (pin "S") (pinfunction "S_S") (pintype "passive"))
      (node (ref "U15") (pin "2") (pinfunction "GND_2") (pintype "passive"))
      (node (ref "U15") (pin "8") (pinfunction "STB_8") (pintype "input"))
      (node (ref "U15") (pin "9") (pinfunction "PGND_9") (pintype "passive"))
      (node (ref "U2") (pin "2") (pinfunction "GND_2") (pintype "passive"))
      (node (ref "U2") (pin "8") (pinfunction "STB_8") (pintype "input"))
      (node (ref "U2") (pin "9") (pinfunction "PGND_9") (pintype "passive"))
      (node (ref "U3") (pin "2") (pinfunction "GND_2") (pintype "passive"))
      (node (ref "U3") (pin "8") (pinfunction "STB_8") (pintype "input"))
      (node (ref "U3") (pin "9") (pinfunction "PGND_9") (pintype "passive"))
    )
    (net (code "34") (name "Net-(C86-Pad1)") (class "Default")
      (node (ref "C86") (pin "1") (pinfunction "1_1") (pintype "passive"))
      (node (ref "R107") (pin "2") (pinfunction "2_2") (pintype "passive"))
      (node (ref "R38") (pin "2") (pinfunction "2_2") (pintype "passive"))
    )
    (net (code "35") (name "Net-(C87-Pad1)") (class "Default")
      (node (ref "C87") (pin "1") (pinfunction "1_1") (pintype "passive"))
      (node (ref "R108") (pin "2") (pinfunction "2_2") (pintype "passive"))
      (node (ref "R109") (pin "2") (pinfunction "2_2") (pintype "passive"))
    )
    (net (code "36") (name "Net-(C92-Pad1)") (class "Default")
      (node (ref "C92") (pin "1") (pinfunction "1_1") (pintype "passive"))
      (node (ref "R111") (pin "2") (pinfunction "2_2") (pintype "passive"))
      (node (ref "R112") (pin "2") (pinfunction "2_2") (pintype "passive"))
    )
    (net (code "37") (name "Net-(D16-PadC)") (class "Default")
      (node (ref "D16") (pin "C") (pinfunction "C_C") (pintype "passive"))
      (node (ref "F8") (pin "1") (pinfunction "1_1") (pintype "passive"))
    )
    (net (code "38") (name "Net-(D17-PadC)") (class "Default")
      (node (ref "D17") (pin "C") (pinfunction "C_C") (pintype "passive"))
      (node (ref "F5") (pin "1") (pinfunction "1_1") (pintype "passive"))
    )
    (net (code "39") (name "Net-(D60-PadC)") (class "Default")
      (node (ref "D60") (pin "C") (pinfunction "C_C") (pintype "passive"))
      (node (ref "F9") (pin "1") (pinfunction "1_1") (pintype "passive"))
    )
    (net (code "40") (name "Net-(U2-VCC)") (class "Default")
      (node (ref "C17") (pin "1") (pinfunction "1_1") (pintype "passive"))
      (node (ref "FB4") (pin "2") (pinfunction "2_2") (pintype "passive"))
      (node (ref "U2") (pin "3") (pinfunction "VCC_3") (pintype "power_in"))
    )
    (net (code "41") (name "Net-(U2-VIO)") (class "Default")
      (node (ref "C14") (pin "1") (pinfunction "1_1") (pintype "passive"))
      (node (ref "FB3") (pin "2") (pinfunction "2_2") (pintype "passive"))
      (node (ref "U2") (pin "5") (pinfunction "VIO_5") (pintype "power_in"))
    )
    (net (code "42") (name "Net-(U3-VCC)") (class "Default")
      (node (ref "C19") (pin "1") (pinfunction "1_1") (pintype "passive"))
      (node (ref "FB6") (pin "2") (pinfunction "2_2") (pintype "passive"))
      (node (ref "U3") (pin "3") (pinfunction "VCC_3") (pintype "power_in"))
    )
    (net (code "43") (name "Net-(U3-VIO)") (class "Default")
      (node (ref "C18") (pin "1") (pinfunction "1_1") (pintype "passive"))
      (node (ref "FB5") (pin "2") (pinfunction "2_2") (pintype "passive"))
      (node (ref "U3") (pin "5") (pinfunction "VIO_5") (pintype "power_in"))
    )
    (net (code "44") (name "Net-(U15-VCC)") (class "Default")
      (node (ref "C89") (pin "1") (pinfunction "1_1") (pintype "passive"))
      (node (ref "FB8") (pin "2") (pinfunction "2_2") (pintype "passive"))
      (node (ref "U15") (pin "3") (pinfunction "VCC_3") (pintype "power_in"))
    )
    (net (code "45") (name "Net-(U15-VIO)") (class "Default")
      (node (ref "C88") (pin "1") (pinfunction "1_1") (pintype "passive"))
      (node (ref "FB7") (pin "2") (pinfunction "2_2") (pintype "passive"))
      (node (ref "U15") (pin "5") (pinfunction "VIO_5") (pintype "power_in"))
    )
    (net (code "46") (name "VDD_5V_PERIPH") (class "Default")
      (node (ref "C21") (pin "1") (pinfunction "1_1") (pintype "passive"))
      (node (ref "D16") (pin "A") (pinfunction "A_A") (pintype "passive"))
      (node (ref "D17") (pin "A") (pinfunction "A_A") (pintype "passive"))
      (node (ref "D60") (pin "A") (pinfunction "A_A") (pintype "passive"))
      (node (ref "F10") (pin "1") (pinfunction "1_1") (pintype "passive"))
      (node (ref "FB4") (pin "1") (pinfunction "1_1") (pintype "passive"))
      (node (ref "FB6") (pin "1") (pinfunction "1_1") (pintype "passive"))
      (node (ref "FB8") (pin "1") (pinfunction "1_1") (pintype "passive"))
    )
    (net (code "47") (name "unconnected-(D27-NC-Pad6)") (class "Default")
      (node (ref "D27") (pin "6") (pinfunction "NC_6") (pintype "passive+no_connect"))
    )
    (net (code "48") (name "unconnected-(D27-NC-Pad10)") (class "Default")
      (node (ref "D27") (pin "10") (pinfunction "NC_10") (pintype "passive+no_connect"))
    )
    (net (code "49") (name "unconnected-(D27-Pad1)") (class "Default")
      (node (ref "D27") (pin "1") (pinfunction "1_1") (pintype "passive+no_connect"))
    )
    (net (code "50") (name "unconnected-(D27-Pad5)") (class "Default")
      (node (ref "D27") (pin "5") (pinfunction "5_5") (pintype "passive+no_connect"))
    )
    (net (code "51") (name "unconnected-(J11-Pad6)") (class "Default")
      (node (ref "J11") (pin "6") (pinfunction "6_6") (pintype "passive+no_connect"))
    )
    (net (code "52") (name "unconnected-(J11-Pad9)") (class "Default")
      (node (ref "J11") (pin "9") (pinfunction "9_9") (pintype "passive+no_connect"))
    )
    (net (code "53") (name "unconnected-(U2-NC-Pad5)") (class "Default")
      (node (ref "U2") (pin "5") (pinfunction "NC_5") (pintype "passive+no_connect"))
    )
    (net (code "54") (name "unconnected-(U3-NC-Pad5)") (class "Default")
      (node (ref "U3") (pin "5") (pinfunction "NC_5") (pintype "passive+no_connect"))
    )
    (net (code "55") (name "unconnected-(U15-NC-Pad5)") (class "Default")
      (node (ref "U15") (pin "5") (pinfunction "NC_5") (pintype "passive+no_connect"))
    )
  )
)
